# 001-03_3.net
KiCad netlist of a schematic drawn in Altium Designer
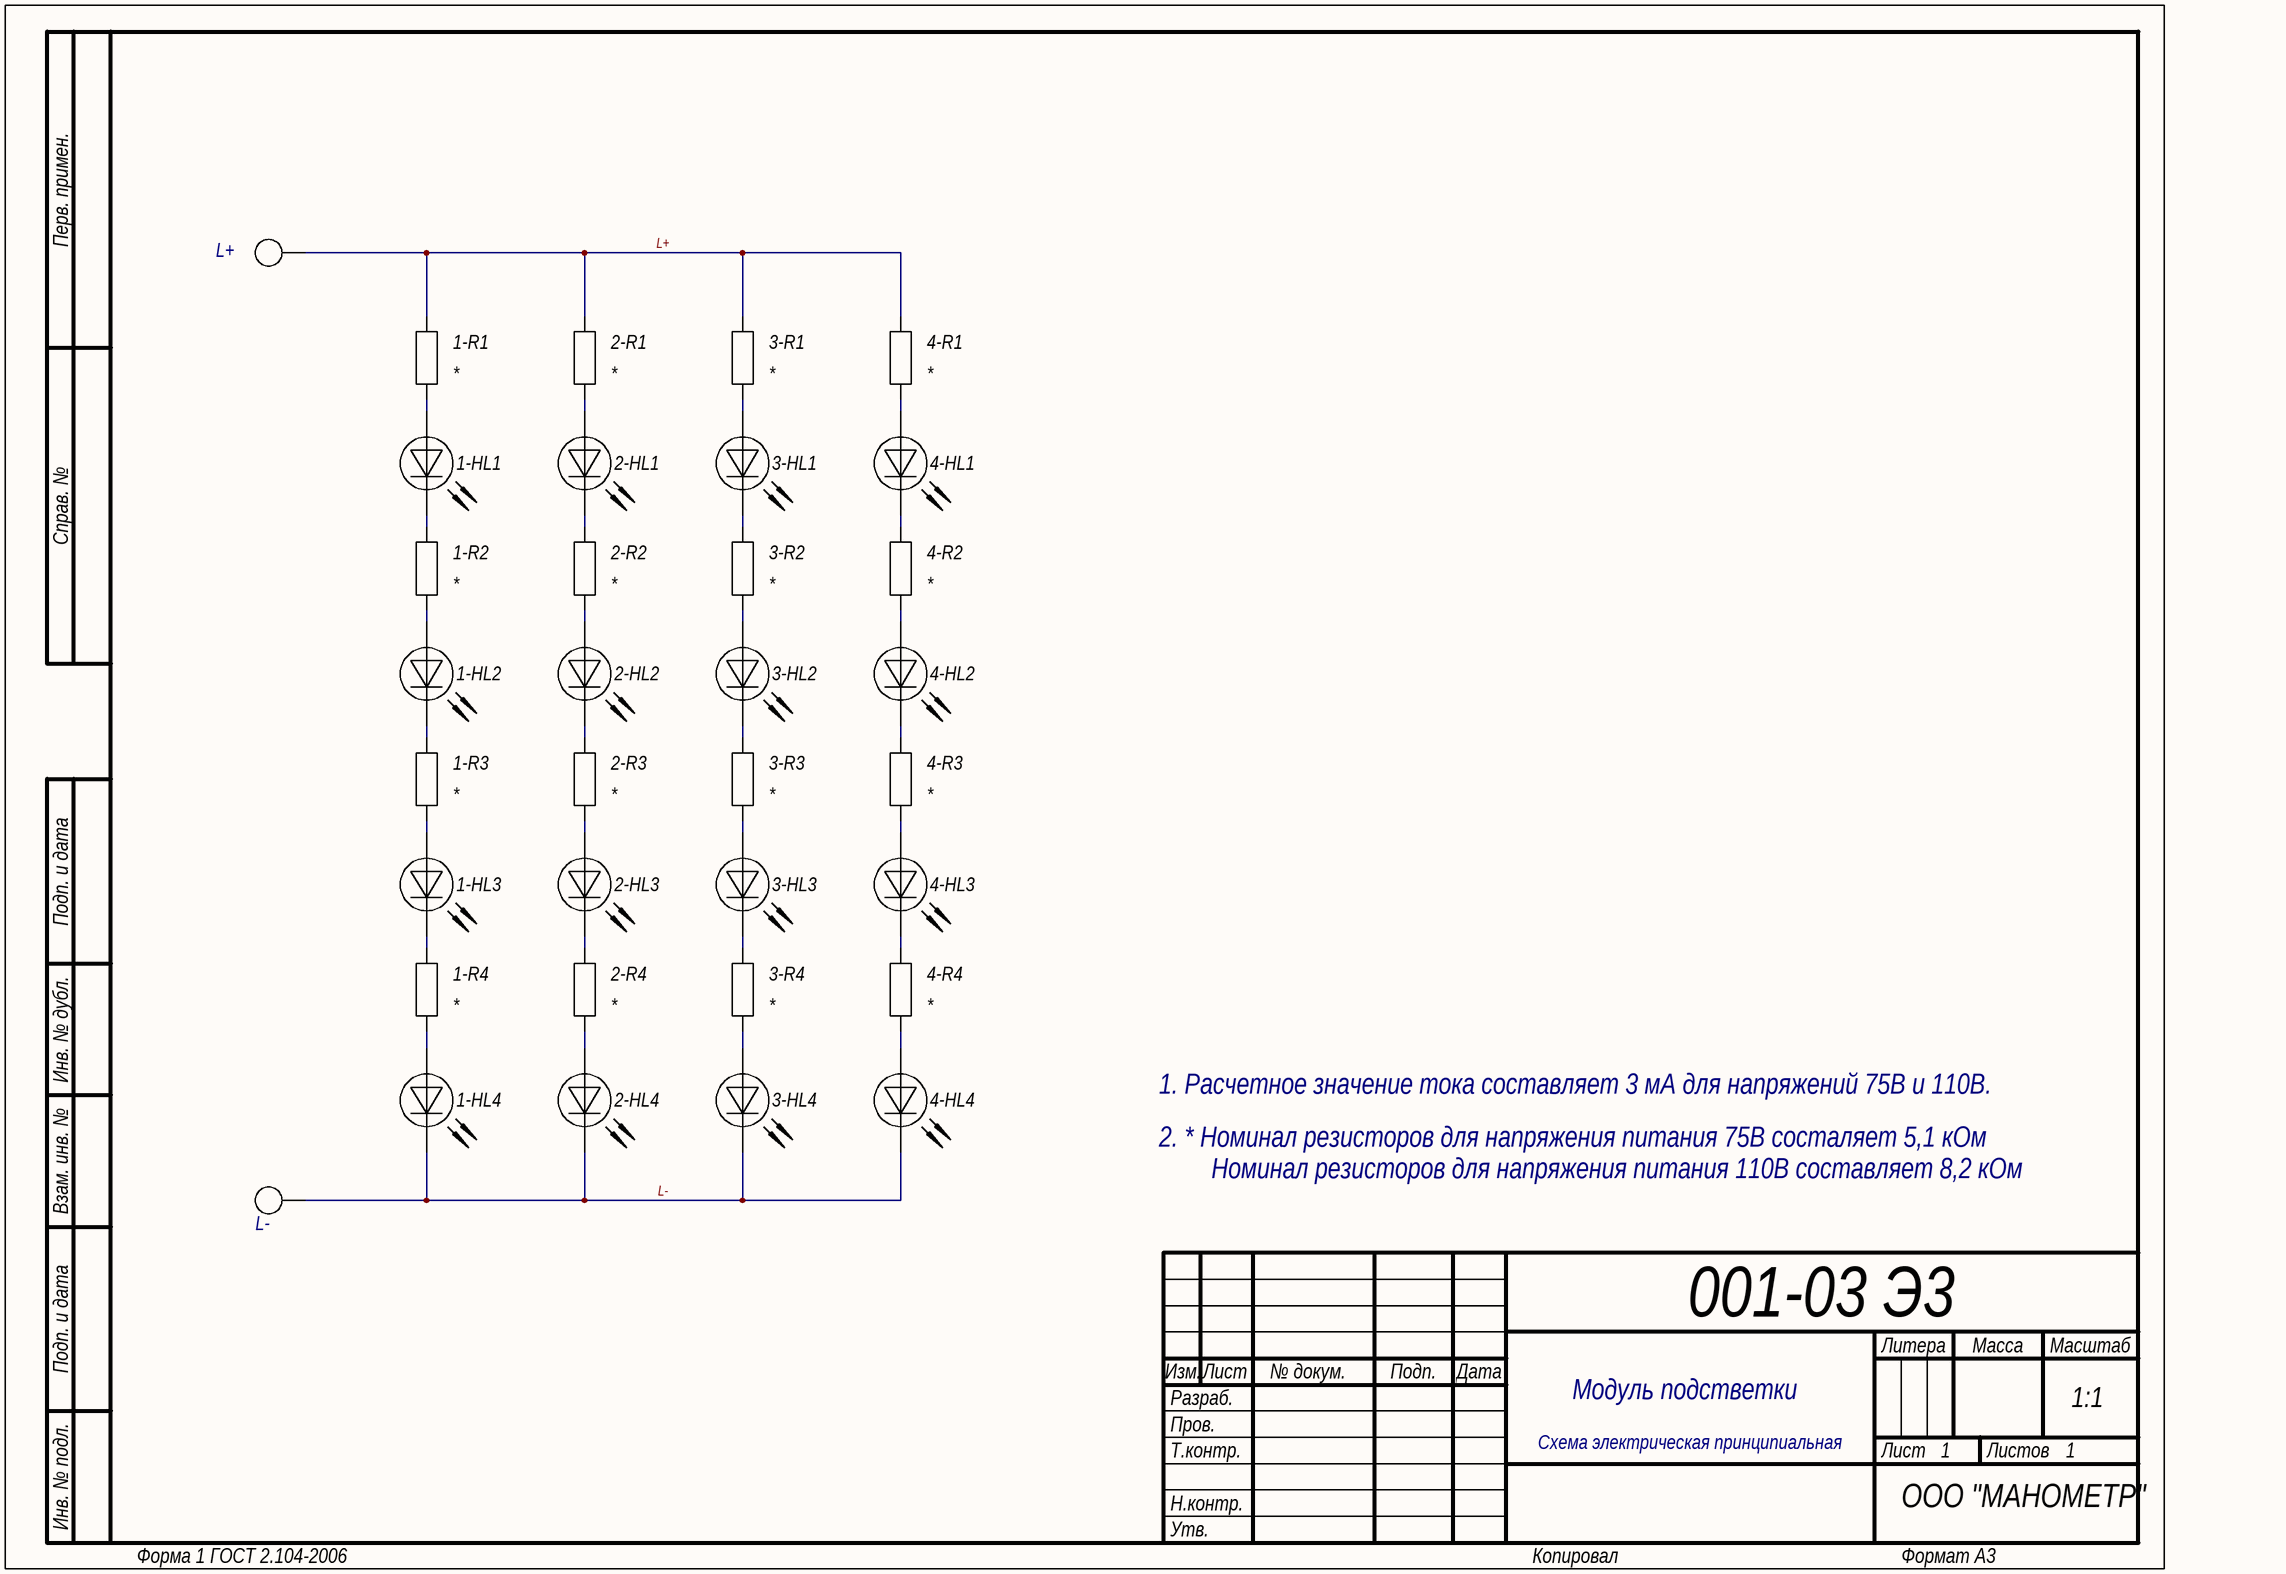
[diagram p0: 001-03 Э3.SchDoc]

(export (version "E")
  (design (tool "Eeschema 10.0.6"))
  (components
    (comp (ref "1-HL1")
      (value "FYLS-1206UWC")
      (footprint "LED 1206")
      (description "Светодиод")
      (fields (field (name "TOLERANCE") "3K*"))
      (libsource (lib "MAXX") (part "LED"))
    )
    (comp (ref "1-HL2")
      (value "FYLS-1206UWC")
      (footprint "LED 1206")
      (description "Светодиод")
      (fields (field (name "TOLERANCE") "3K*"))
      (libsource (lib "MAXX") (part "LED"))
    )
    (comp (ref "1-HL3")
      (value "FYLS-1206UWC")
      (footprint "LED 1206")
      (description "Светодиод")
      (fields (field (name "TOLERANCE") "3K*"))
      (libsource (lib "MAXX") (part "LED"))
    )
    (comp (ref "1-HL4")
      (value "FYLS-1206UWC")
      (footprint "LED 1206")
      (description "Светодиод")
      (fields (field (name "TOLERANCE") "3K*"))
      (libsource (lib "MAXX") (part "LED"))
    )
    (comp (ref "1-R1")
      (value "*")
      (footprint "RC1206")
      (description "Постоянный углеродистый резистор")
      (fields (field (name "TOLERANCE") "3K*"))
      (libsource (lib "MAXX") (part "RES"))
    )
    (comp (ref "1-R2")
      (value "*")
      (footprint "RC1206")
      (description "Постоянный углеродистый резистор")
      (fields (field (name "TOLERANCE") "3K*"))
      (libsource (lib "MAXX") (part "RES"))
    )
    (comp (ref "1-R3")
      (value "*")
      (footprint "RC1206")
      (description "Постоянный углеродистый резистор")
      (fields (field (name "TOLERANCE") "3K*"))
      (libsource (lib "MAXX") (part "RES"))
    )
    (comp (ref "1-R4")
      (value "*")
      (footprint "RC1206")
      (description "Постоянный углеродистый резистор")
      (fields (field (name "TOLERANCE") "3K*"))
      (libsource (lib "MAXX") (part "RES"))
    )
    (comp (ref "2-HL1")
      (value "FYLS-1206UWC")
      (footprint "LED 1206")
      (description "Светодиод")
      (fields (field (name "TOLERANCE") "3K*"))
      (libsource (lib "MAXX") (part "LED"))
    )
    (comp (ref "2-HL2")
      (value "FYLS-1206UWC")
      (footprint "LED 1206")
      (description "Светодиод")
      (fields (field (name "TOLERANCE") "3K*"))
      (libsource (lib "MAXX") (part "LED"))
    )
    (comp (ref "2-HL3")
      (value "FYLS-1206UWC")
      (footprint "LED 1206")
      (description "Светодиод")
      (fields (field (name "TOLERANCE") "3K*"))
      (libsource (lib "MAXX") (part "LED"))
    )
    (comp (ref "2-HL4")
      (value "FYLS-1206UWC")
      (footprint "LED 1206")
      (description "Светодиод")
      (fields (field (name "TOLERANCE") "3K*"))
      (libsource (lib "MAXX") (part "LED"))
    )
    (comp (ref "2-R1")
      (value "*")
      (footprint "RC1206")
      (description "Постоянный углеродистый резистор")
      (fields (field (name "TOLERANCE") "3K*"))
      (libsource (lib "MAXX") (part "RES"))
    )
    (comp (ref "2-R2")
      (value "*")
      (footprint "RC1206")
      (description "Постоянный углеродистый резистор")
      (fields (field (name "TOLERANCE") "3K*"))
      (libsource (lib "MAXX") (part "RES"))
    )
    (comp (ref "2-R3")
      (value "*")
      (footprint "RC1206")
      (description "Постоянный углеродистый резистор")
      (fields (field (name "TOLERANCE") "3K*"))
      (libsource (lib "MAXX") (part "RES"))
    )
    (comp (ref "2-R4")
      (value "*")
      (footprint "RC1206")
      (description "Постоянный углеродистый резистор")
      (fields (field (name "TOLERANCE") "3K*"))
      (libsource (lib "MAXX") (part "RES"))
    )
    (comp (ref "3-HL1")
      (value "FYLS-1206UWC")
      (footprint "LED 1206")
      (description "Светодиод")
      (fields (field (name "TOLERANCE") "3K*"))
      (libsource (lib "MAXX") (part "LED"))
    )
    (comp (ref "3-HL2")
      (value "FYLS-1206UWC")
      (footprint "LED 1206")
      (description "Светодиод")
      (fields (field (name "TOLERANCE") "3K*"))
      (libsource (lib "MAXX") (part "LED"))
    )
    (comp (ref "3-HL3")
      (value "FYLS-1206UWC")
      (footprint "LED 1206")
      (description "Светодиод")
      (fields (field (name "TOLERANCE") "3K*"))
      (libsource (lib "MAXX") (part "LED"))
    )
    (comp (ref "3-HL4")
      (value "FYLS-1206UWC")
      (footprint "LED 1206")
      (description "Светодиод")
      (fields (field (name "TOLERANCE") "3K*"))
      (libsource (lib "MAXX") (part "LED"))
    )
    (comp (ref "3-R1")
      (value "*")
      (footprint "RC1206")
      (description "Постоянный углеродистый резистор")
      (fields (field (name "TOLERANCE") "3K*"))
      (libsource (lib "MAXX") (part "RES"))
    )
    (comp (ref "3-R2")
      (value "*")
      (footprint "RC1206")
      (description "Постоянный углеродистый резистор")
      (fields (field (name "TOLERANCE") "3K*"))
      (libsource (lib "MAXX") (part "RES"))
    )
    (comp (ref "3-R3")
      (value "*")
      (footprint "RC1206")
      (description "Постоянный углеродистый резистор")
      (fields (field (name "TOLERANCE") "3K*"))
      (libsource (lib "MAXX") (part "RES"))
    )
    (comp (ref "3-R4")
      (value "*")
      (footprint "RC1206")
      (description "Постоянный углеродистый резистор")
      (fields (field (name "TOLERANCE") "3K*"))
      (libsource (lib "MAXX") (part "RES"))
    )
    (comp (ref "4-HL1")
      (value "FYLS-1206UWC")
      (footprint "LED 1206")
      (description "Светодиод")
      (fields (field (name "TOLERANCE") "3K*"))
      (libsource (lib "MAXX") (part "LED"))
    )
    (comp (ref "4-HL2")
      (value "FYLS-1206UWC")
      (footprint "LED 1206")
      (description "Светодиод")
      (fields (field (name "TOLERANCE") "3K*"))
      (libsource (lib "MAXX") (part "LED"))
    )
    (comp (ref "4-HL3")
      (value "FYLS-1206UWC")
      (footprint "LED 1206")
      (description "Светодиод")
      (fields (field (name "TOLERANCE") "3K*"))
      (libsource (lib "MAXX") (part "LED"))
    )
    (comp (ref "4-HL4")
      (value "FYLS-1206UWC")
      (footprint "LED 1206")
      (description "Светодиод")
      (fields (field (name "TOLERANCE") "3K*"))
      (libsource (lib "MAXX") (part "LED"))
    )
    (comp (ref "4-R1")
      (value "*")
      (footprint "RC1206")
      (description "Постоянный углеродистый резистор")
      (fields (field (name "TOLERANCE") "3K*"))
      (libsource (lib "MAXX") (part "RES"))
    )
    (comp (ref "4-R2")
      (value "*")
      (footprint "RC1206")
      (description "Постоянный углеродистый резистор")
      (fields (field (name "TOLERANCE") "3K*"))
      (libsource (lib "MAXX") (part "RES"))
    )
    (comp (ref "4-R3")
      (value "*")
      (footprint "RC1206")
      (description "Постоянный углеродистый резистор")
      (fields (field (name "TOLERANCE") "3K*"))
      (libsource (lib "MAXX") (part "RES"))
    )
    (comp (ref "4-R4")
      (value "*")
      (footprint "RC1206")
      (description "Постоянный углеродистый резистор")
      (fields (field (name "TOLERANCE") "3K*"))
      (libsource (lib "MAXX") (part "RES"))
    )
    (comp (ref "L+") (value "~") (footprint "PIN") (libsource (lib "MAXX") (part "PIN")))
    (comp (ref "L-") (value "~") (footprint "PIN") (libsource (lib "MAXX") (part "PIN")))
  )
  (nets
    (net (code "1") (name "/L+") (class "Default")
      (node (ref "1-R1") (pin "1") (pinfunction "1_1") (pintype "passive"))
      (node (ref "2-R1") (pin "1") (pinfunction "1_1") (pintype "passive"))
      (node (ref "3-R1") (pin "1") (pinfunction "1_1") (pintype "passive"))
      (node (ref "4-R1") (pin "1") (pinfunction "1_1") (pintype "passive"))
      (node (ref "L+") (pin "PIN") (pinfunction "PIN_PIN") (pintype "passive"))
    )
    (net (code "2") (name "/L-") (class "Default")
      (node (ref "1-HL4") (pin "2") (pinfunction "K_2") (pintype "passive"))
      (node (ref "2-HL4") (pin "2") (pinfunction "K_2") (pintype "passive"))
      (node (ref "3-HL4") (pin "2") (pinfunction "K_2") (pintype "passive"))
      (node (ref "4-HL4") (pin "2") (pinfunction "K_2") (pintype "passive"))
      (node (ref "L-") (pin "PIN") (pinfunction "PIN_PIN") (pintype "passive"))
    )
    (net (code "3") (name "Net-(1-HL1-A)") (class "Default")
      (node (ref "1-HL1") (pin "1") (pinfunction "A_1") (pintype "passive"))
      (node (ref "1-R1") (pin "2") (pinfunction "2_2") (pintype "passive"))
    )
    (net (code "4") (name "Net-(1-HL1-K)") (class "Default")
      (node (ref "1-HL1") (pin "2") (pinfunction "K_2") (pintype "passive"))
      (node (ref "1-R2") (pin "1") (pinfunction "1_1") (pintype "passive"))
    )
    (net (code "5") (name "Net-(1-HL2-A)") (class "Default")
      (node (ref "1-HL2") (pin "1") (pinfunction "A_1") (pintype "passive"))
      (node (ref "1-R2") (pin "2") (pinfunction "2_2") (pintype "passive"))
    )
    (net (code "6") (name "Net-(1-HL2-K)") (class "Default")
      (node (ref "1-HL2") (pin "2") (pinfunction "K_2") (pintype "passive"))
      (node (ref "1-R3") (pin "1") (pinfunction "1_1") (pintype "passive"))
    )
    (net (code "7") (name "Net-(1-HL3-A)") (class "Default")
      (node (ref "1-HL3") (pin "1") (pinfunction "A_1") (pintype "passive"))
      (node (ref "1-R3") (pin "2") (pinfunction "2_2") (pintype "passive"))
    )
    (net (code "8") (name "Net-(1-HL3-K)") (class "Default")
      (node (ref "1-HL3") (pin "2") (pinfunction "K_2") (pintype "passive"))
      (node (ref "1-R4") (pin "1") (pinfunction "1_1") (pintype "passive"))
    )
    (net (code "9") (name "Net-(1-HL4-A)") (class "Default")
      (node (ref "1-HL4") (pin "1") (pinfunction "A_1") (pintype "passive"))
      (node (ref "1-R4") (pin "2") (pinfunction "2_2") (pintype "passive"))
    )
    (net (code "10") (name "Net-(2-HL1-A)") (class "Default")
      (node (ref "2-HL1") (pin "1") (pinfunction "A_1") (pintype "passive"))
      (node (ref "2-R1") (pin "2") (pinfunction "2_2") (pintype "passive"))
    )
    (net (code "11") (name "Net-(2-HL1-K)") (class "Default")
      (node (ref "2-HL1") (pin "2") (pinfunction "K_2") (pintype "passive"))
      (node (ref "2-R2") (pin "1") (pinfunction "1_1") (pintype "passive"))
    )
    (net (code "12") (name "Net-(2-HL2-A)") (class "Default")
      (node (ref "2-HL2") (pin "1") (pinfunction "A_1") (pintype "passive"))
      (node (ref "2-R2") (pin "2") (pinfunction "2_2") (pintype "passive"))
    )
    (net (code "13") (name "Net-(2-HL2-K)") (class "Default")
      (node (ref "2-HL2") (pin "2") (pinfunction "K_2") (pintype "passive"))
      (node (ref "2-R3") (pin "1") (pinfunction "1_1") (pintype "passive"))
    )
    (net (code "14") (name "Net-(2-HL3-A)") (class "Default")
      (node (ref "2-HL3") (pin "1") (pinfunction "A_1") (pintype "passive"))
      (node (ref "2-R3") (pin "2") (pinfunction "2_2") (pintype "passive"))
    )
    (net (code "15") (name "Net-(2-HL3-K)") (class "Default")
      (node (ref "2-HL3") (pin "2") (pinfunction "K_2") (pintype "passive"))
      (node (ref "2-R4") (pin "1") (pinfunction "1_1") (pintype "passive"))
    )
    (net (code "16") (name "Net-(2-HL4-A)") (class "Default")
      (node (ref "2-HL4") (pin "1") (pinfunction "A_1") (pintype "passive"))
      (node (ref "2-R4") (pin "2") (pinfunction "2_2") (pintype "passive"))
    )
    (net (code "17") (name "Net-(3-HL1-A)") (class "Default")
      (node (ref "3-HL1") (pin "1") (pinfunction "A_1") (pintype "passive"))
      (node (ref "3-R1") (pin "2") (pinfunction "2_2") (pintype "passive"))
    )
    (net (code "18") (name "Net-(3-HL1-K)") (class "Default")
      (node (ref "3-HL1") (pin "2") (pinfunction "K_2") (pintype "passive"))
      (node (ref "3-R2") (pin "1") (pinfunction "1_1") (pintype "passive"))
    )
    (net (code "19") (name "Net-(3-HL2-A)") (class "Default")
      (node (ref "3-HL2") (pin "1") (pinfunction "A_1") (pintype "passive"))
      (node (ref "3-R2") (pin "2") (pinfunction "2_2") (pintype "passive"))
    )
    (net (code "20") (name "Net-(3-HL2-K)") (class "Default")
      (node (ref "3-HL2") (pin "2") (pinfunction "K_2") (pintype "passive"))
      (node (ref "3-R3") (pin "1") (pinfunction "1_1") (pintype "passive"))
    )
    (net (code "21") (name "Net-(3-HL3-A)") (class "Default")
      (node (ref "3-HL3") (pin "1") (pinfunction "A_1") (pintype "passive"))
      (node (ref "3-R3") (pin "2") (pinfunction "2_2") (pintype "passive"))
    )
    (net (code "22") (name "Net-(3-HL3-K)") (class "Default")
      (node (ref "3-HL3") (pin "2") (pinfunction "K_2") (pintype "passive"))
      (node (ref "3-R4") (pin "1") (pinfunction "1_1") (pintype "passive"))
    )
    (net (code "23") (name "Net-(3-HL4-A)") (class "Default")
      (node (ref "3-HL4") (pin "1") (pinfunction "A_1") (pintype "passive"))
      (node (ref "3-R4") (pin "2") (pinfunction "2_2") (pintype "passive"))
    )
    (net (code "24") (name "Net-(4-HL1-A)") (class "Default")
      (node (ref "4-HL1") (pin "1") (pinfunction "A_1") (pintype "passive"))
      (node (ref "4-R1") (pin "2") (pinfunction "2_2") (pintype "passive"))
    )
    (net (code "25") (name "Net-(4-HL1-K)") (class "Default")
      (node (ref "4-HL1") (pin "2") (pinfunction "K_2") (pintype "passive"))
      (node (ref "4-R2") (pin "1") (pinfunction "1_1") (pintype "passive"))
    )
    (net (code "26") (name "Net-(4-HL2-A)") (class "Default")
      (node (ref "4-HL2") (pin "1") (pinfunction "A_1") (pintype "passive"))
      (node (ref "4-R2") (pin "2") (pinfunction "2_2") (pintype "passive"))
    )
    (net (code "27") (name "Net-(4-HL2-K)") (class "Default")
      (node (ref "4-HL2") (pin "2") (pinfunction "K_2") (pintype "passive"))
      (node (ref "4-R3") (pin "1") (pinfunction "1_1") (pintype "passive"))
    )
    (net (code "28") (name "Net-(4-HL3-A)") (class "Default")
      (node (ref "4-HL3") (pin "1") (pinfunction "A_1") (pintype "passive"))
      (node (ref "4-R3") (pin "2") (pinfunction "2_2") (pintype "passive"))
    )
    (net (code "29") (name "Net-(4-HL3-K)") (class "Default")
      (node (ref "4-HL3") (pin "2") (pinfunction "K_2") (pintype "passive"))
      (node (ref "4-R4") (pin "1") (pinfunction "1_1") (pintype "passive"))
    )
    (net (code "30") (name "Net-(4-HL4-A)") (class "Default")
      (node (ref "4-HL4") (pin "1") (pinfunction "A_1") (pintype "passive"))
      (node (ref "4-R4") (pin "2") (pinfunction "2_2") (pintype "passive"))
    )
  )
)
